# ProPrj_AD__2025-10-15.net
KiCad netlist of a schematic drawn in EasyEDA Pro
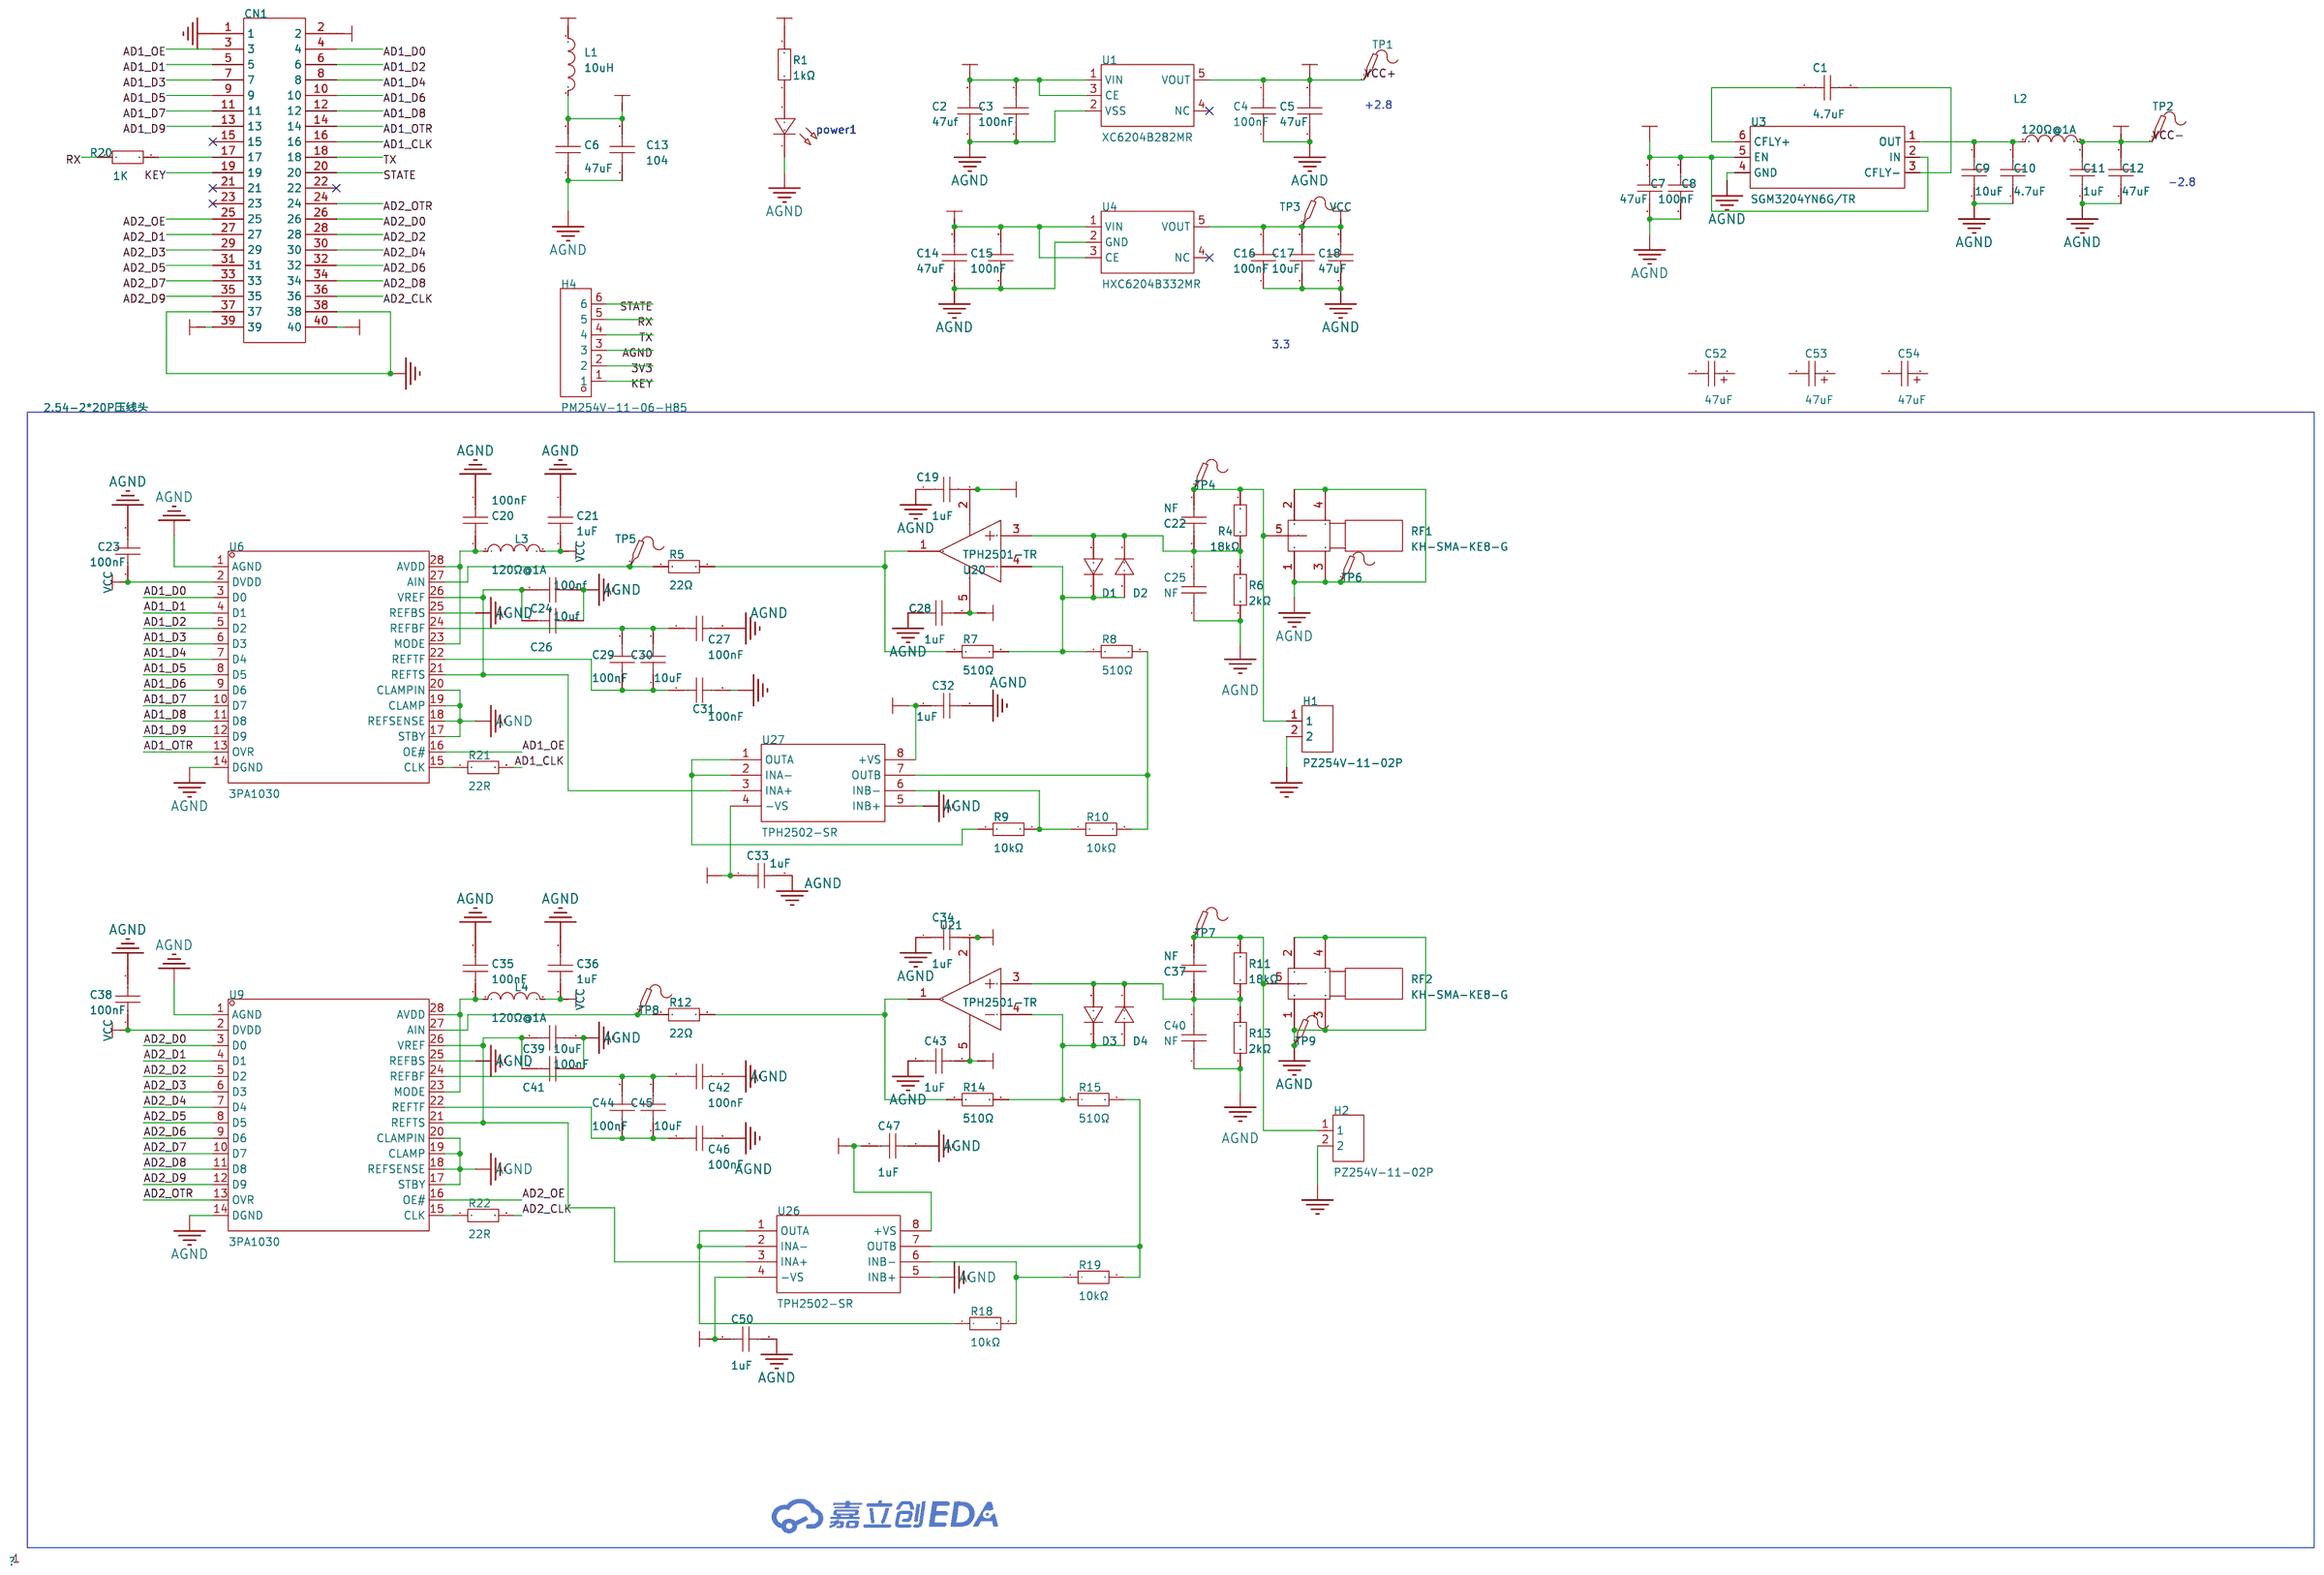
[diagram p0: schematic sheet]

(export (version "E")
  (design (tool "Eeschema 10.0.6"))
  (components
    (comp (ref "C1")
      (value "4.7uF")
      (footprint "easyedapro:C0603")
      (libsource (lib "easyedapro") (part "Capacitance"))
    )
    (comp (ref "C2")
      (value "47uf")
      (footprint "easyedapro:C0603")
      (libsource (lib "easyedapro") (part "Capacitance"))
    )
    (comp (ref "C3")
      (value "100nF")
      (footprint "easyedapro:C0603")
      (libsource (lib "easyedapro") (part "Capacitance"))
    )
    (comp (ref "C4")
      (value "100nF")
      (footprint "easyedapro:C0603")
      (libsource (lib "easyedapro") (part "Capacitance"))
    )
    (comp (ref "C5")
      (value "47uF")
      (footprint "easyedapro:C0603")
      (libsource (lib "easyedapro") (part "Capacitance"))
    )
    (comp (ref "C6")
      (value "47uF")
      (footprint "easyedapro:C0603")
      (libsource (lib "easyedapro") (part "Capacitance"))
    )
    (comp (ref "C7")
      (value "47uF")
      (footprint "easyedapro:C0603")
      (libsource (lib "easyedapro") (part "Capacitance"))
    )
    (comp (ref "C8")
      (value "100nF")
      (footprint "easyedapro:C0603")
      (libsource (lib "easyedapro") (part "Capacitance"))
    )
    (comp (ref "C9")
      (value "10uF")
      (footprint "easyedapro:C0603")
      (libsource (lib "easyedapro") (part "Capacitance"))
    )
    (comp (ref "C10")
      (value "4.7uF")
      (footprint "easyedapro:C0603")
      (libsource (lib "easyedapro") (part "Capacitance"))
    )
    (comp (ref "C11")
      (value "1uF")
      (footprint "easyedapro:C0603")
      (libsource (lib "easyedapro") (part "Capacitance"))
    )
    (comp (ref "C12")
      (value "47uF")
      (footprint "easyedapro:C0603")
      (libsource (lib "easyedapro") (part "Capacitance"))
    )
    (comp (ref "C13")
      (value "100nF")
      (footprint "easyedapro:C0603")
      (libsource (lib "easyedapro") (part "Capacitance"))
    )
    (comp (ref "C14")
      (value "47uF")
      (footprint "easyedapro:C0603")
      (libsource (lib "easyedapro") (part "Capacitance"))
    )
    (comp (ref "C15")
      (value "100nF")
      (footprint "easyedapro:C0603")
      (libsource (lib "easyedapro") (part "Capacitance"))
    )
    (comp (ref "C16")
      (value "100nF")
      (footprint "easyedapro:C0603")
      (libsource (lib "easyedapro") (part "Capacitance"))
    )
    (comp (ref "C17")
      (value "10uF")
      (footprint "easyedapro:C0603")
      (libsource (lib "easyedapro") (part "Capacitance"))
    )
    (comp (ref "C18")
      (value "47uF")
      (footprint "easyedapro:C0603")
      (libsource (lib "easyedapro") (part "Capacitance"))
    )
    (comp (ref "C19")
      (value "1uF")
      (footprint "easyedapro:C0603")
      (libsource (lib "easyedapro") (part "Capacitance"))
    )
    (comp (ref "C20")
      (value "100nF")
      (footprint "easyedapro:C0603")
      (libsource (lib "easyedapro") (part "Capacitance"))
    )
    (comp (ref "C21")
      (value "1uF")
      (footprint "easyedapro:C0603")
      (libsource (lib "easyedapro") (part "Capacitance"))
    )
    (comp (ref "C22")
      (value "NF")
      (footprint "easyedapro:C0603")
      (libsource (lib "easyedapro") (part "Capacitance"))
    )
    (comp (ref "C23")
      (value "100nF")
      (footprint "easyedapro:C0603")
      (libsource (lib "easyedapro") (part "Capacitance"))
    )
    (comp (ref "C24")
      (value "100nf")
      (footprint "easyedapro:C0603")
      (libsource (lib "easyedapro") (part "Capacitance"))
    )
    (comp (ref "C25")
      (value "NF")
      (footprint "easyedapro:C0603")
      (libsource (lib "easyedapro") (part "Capacitance"))
    )
    (comp (ref "C26")
      (value "10uf")
      (footprint "easyedapro:C0603")
      (libsource (lib "easyedapro") (part "Capacitance"))
    )
    (comp (ref "C27")
      (value "100nF")
      (footprint "easyedapro:C0603")
      (libsource (lib "easyedapro") (part "Capacitance"))
    )
    (comp (ref "C28")
      (value "1uF")
      (footprint "easyedapro:C0603")
      (libsource (lib "easyedapro") (part "Capacitance"))
    )
    (comp (ref "C29")
      (value "100nF")
      (footprint "easyedapro:C0603")
      (libsource (lib "easyedapro") (part "Capacitance"))
    )
    (comp (ref "C30")
      (value "10uF")
      (footprint "easyedapro:C0603")
      (libsource (lib "easyedapro") (part "Capacitance"))
    )
    (comp (ref "C31")
      (value "100nF")
      (footprint "easyedapro:C0603")
      (libsource (lib "easyedapro") (part "Capacitance"))
    )
    (comp (ref "C32")
      (value "1uF")
      (footprint "easyedapro:C0603")
      (libsource (lib "easyedapro") (part "Capacitance"))
    )
    (comp (ref "C33")
      (value "1uF")
      (footprint "easyedapro:C0603")
      (libsource (lib "easyedapro") (part "Capacitance"))
    )
    (comp (ref "C34")
      (value "1uF")
      (footprint "easyedapro:C0603")
      (libsource (lib "easyedapro") (part "Capacitance"))
    )
    (comp (ref "C35")
      (value "100nF")
      (footprint "easyedapro:C0603")
      (libsource (lib "easyedapro") (part "Capacitance"))
    )
    (comp (ref "C36")
      (value "1uF")
      (footprint "easyedapro:C0603")
      (libsource (lib "easyedapro") (part "Capacitance"))
    )
    (comp (ref "C37")
      (value "NF")
      (footprint "easyedapro:C0603")
      (libsource (lib "easyedapro") (part "Capacitance"))
    )
    (comp (ref "C38")
      (value "100nF")
      (footprint "easyedapro:C0603")
      (libsource (lib "easyedapro") (part "Capacitance"))
    )
    (comp (ref "C39")
      (value "10uF")
      (footprint "easyedapro:C0603")
      (libsource (lib "easyedapro") (part "Capacitance"))
    )
    (comp (ref "C40")
      (value "NF")
      (footprint "easyedapro:C0603")
      (libsource (lib "easyedapro") (part "Capacitance"))
    )
    (comp (ref "C41")
      (value "100nF")
      (footprint "easyedapro:C0603")
      (libsource (lib "easyedapro") (part "Capacitance"))
    )
    (comp (ref "C42")
      (value "100nF")
      (footprint "easyedapro:C0603")
      (libsource (lib "easyedapro") (part "Capacitance"))
    )
    (comp (ref "C43")
      (value "1uF")
      (footprint "easyedapro:C0603")
      (libsource (lib "easyedapro") (part "Capacitance"))
    )
    (comp (ref "C44")
      (value "100nF")
      (footprint "easyedapro:C0603")
      (libsource (lib "easyedapro") (part "Capacitance"))
    )
    (comp (ref "C45")
      (value "10uF")
      (footprint "easyedapro:C0603")
      (libsource (lib "easyedapro") (part "Capacitance"))
    )
    (comp (ref "C46")
      (value "100nF")
      (footprint "easyedapro:C0603")
      (libsource (lib "easyedapro") (part "Capacitance"))
    )
    (comp (ref "C47")
      (value "1uF")
      (footprint "easyedapro:C0603")
      (libsource (lib "easyedapro") (part "Capacitance"))
    )
    (comp (ref "C50")
      (value "1uF")
      (footprint "easyedapro:C0603")
      (libsource (lib "easyedapro") (part "Capacitance"))
    )
    (comp (ref "C52")
      (value "47uF")
      (footprint "easyedapro:CASE-D_7343")
      (description "容值:47uF;精度:±10%;额定电压:16V;等效串联电阻:900mΩ@100kHz;")
      (fields (field (name "Manufacturer Part") "TAJD476K016RNJ") (field (name "Manufacturer") "Kyocera AVX"))
      (libsource (lib "easyedapro") (part "TAJD476K016RNJ"))
    )
    (comp (ref "C53")
      (value "47uF")
      (footprint "easyedapro:CASE-D_7343")
      (description "容值:47uF;精度:±10%;额定电压:16V;等效串联电阻:900mΩ@100kHz;")
      (fields (field (name "Manufacturer Part") "TAJD476K016RNJ") (field (name "Manufacturer") "Kyocera AVX"))
      (libsource (lib "easyedapro") (part "TAJD476K016RNJ"))
    )
    (comp (ref "C54")
      (value "47uF")
      (footprint "easyedapro:CASE-D_7343")
      (description "容值:47uF;精度:±10%;额定电压:16V;等效串联电阻:900mΩ@100kHz;")
      (fields (field (name "Manufacturer Part") "TAJD476K016RNJ") (field (name "Manufacturer") "Kyocera AVX"))
      (libsource (lib "easyedapro") (part "TAJD476K016RNJ"))
    )
    (comp (ref "CN1")
      (value "2.54-2*20P压线头")
      (footprint "easyedapro:HDR-TH_40P-V-H-R2-P2.54")
      (description "连接器类型:IDC连接器;间距:2.54mm;安装方式:三件式(连接器+压排+反折盖);行距:2.54mm;排数:2;触头材质:黄铜;触头镀层:金;")
      (fields (field (name "Manufacturer") "BOOMELE(博穆精密)"))
      (libsource (lib "easyedapro") (part "Crimping terminals2*20"))
    )
    (comp (ref "D1")
      (value "1N4148W")
      (footprint "easyedapro:SOD-123F_L2.7-W1.6-LS3.8-RD")
      (description "二极管配置:独立式;正向压降(Vf):1V@50mA;直流反向耐压(Vr):75V;整流电流:150mA;反向恢复时间(Trr):4ns;")
      (fields (field (name "Manufacturer") "ST(先科)"))
      (libsource (lib "easyedapro") (part "1N4148W_C81598"))
    )
    (comp (ref "D2")
      (value "1N4148W")
      (footprint "easyedapro:SOD-123F_L2.7-W1.6-LS3.8-RD")
      (description "二极管配置:独立式;正向压降(Vf):1V@50mA;直流反向耐压(Vr):75V;整流电流:150mA;反向恢复时间(Trr):4ns;")
      (fields (field (name "Manufacturer") "ST(先科)"))
      (libsource (lib "easyedapro") (part "1N4148W_C81598"))
    )
    (comp (ref "D3")
      (value "1N4148W")
      (footprint "easyedapro:SOD-123F_L2.7-W1.6-LS3.8-RD")
      (description "二极管配置:独立式;正向压降(Vf):1V@50mA;直流反向耐压(Vr):75V;整流电流:150mA;反向恢复时间(Trr):4ns;")
      (fields (field (name "Manufacturer") "ST(先科)"))
      (libsource (lib "easyedapro") (part "1N4148W_C81598"))
    )
    (comp (ref "D4")
      (value "1N4148W")
      (footprint "easyedapro:SOD-123F_L2.7-W1.6-LS3.8-RD")
      (description "二极管配置:独立式;正向压降(Vf):1V@50mA;直流反向耐压(Vr):75V;整流电流:150mA;反向恢复时间(Trr):4ns;")
      (fields (field (name "Manufacturer") "ST(先科)"))
      (libsource (lib "easyedapro") (part "1N4148W_C81598"))
    )
    (comp (ref "H1")
      (value "PZ254V-11-02P")
      (footprint "easyedapro:HDR-TH_2P-P2.54-V-M")
      (fields (field (name "Manufacturer") "XFCN(兴飞)"))
      (libsource (lib "easyedapro") (part "PZ254V-11-02P"))
    )
    (comp (ref "H2")
      (value "PZ254V-11-02P")
      (footprint "easyedapro:HDR-TH_2P-P2.54-V-M")
      (fields (field (name "Manufacturer") "XFCN(兴飞)"))
      (libsource (lib "easyedapro") (part "PZ254V-11-02P"))
    )
    (comp (ref "H4")
      (value "PM254V-11-06-H85")
      (footprint "easyedapro:HDR-TH_6P-P2.54-V-F")
      (fields (field (name "Manufacturer") "XFCN(兴飞)"))
      (libsource (lib "easyedapro") (part "PM254V-11-06-H85"))
    )
    (comp (ref "L1")
      (value "10uH")
      (footprint "easyedapro:L0603")
      (description "电感值:10uH;精度:±10%;额定电流:3mA;饱和电流(Isat):-;直流电阻(DCR):1.85Ω;")
      (fields
        (field (name "Manufacturer Part") "SDFL1608S100KTF")
        (field (name "Manufacturer") "Sunlord(顺络)")
      )
      (libsource (lib "easyedapro") (part "SDFL1608S100KTF"))
    )
    (comp (ref "L2")
      (value "120Ω@1A")
      (footprint "easyedapro:L0603")
      (description "电感值:10uH;精度:±10%;额定电流:3mA;饱和电流(Isat):-;直流电阻(DCR):1.85Ω;")
      (fields
        (field (name "Manufacturer Part") "SDFL1608S100KTF")
        (field (name "Manufacturer") "Sunlord(顺络)")
      )
      (libsource (lib "easyedapro") (part "SDFL1608S100KTF"))
    )
    (comp (ref "L3")
      (value "120Ω@1A")
      (footprint "easyedapro:L0603")
      (description "电感值:10uH;精度:±10%;额定电流:3mA;饱和电流(Isat):-;直流电阻(DCR):1.85Ω;")
      (fields
        (field (name "Manufacturer Part") "SDFL1608S100KTF")
        (field (name "Manufacturer") "Sunlord(顺络)")
      )
      (libsource (lib "easyedapro") (part "SDFL1608S100KTF"))
    )
    (comp (ref "L4")
      (value "120Ω@1A")
      (footprint "easyedapro:L0603")
      (description "电感值:10uH;精度:±10%;额定电流:3mA;饱和电流(Isat):-;直流电阻(DCR):1.85Ω;")
      (fields
        (field (name "Manufacturer Part") "SDFL1608S100KTF")
        (field (name "Manufacturer") "Sunlord(顺络)")
      )
      (libsource (lib "easyedapro") (part "SDFL1608S100KTF"))
    )
    (comp (ref "power1")
      (value "LTST-C193TBKT-5A")
      (footprint "easyedapro:LED_0603")
      (libsource (lib "easyedapro") (part "LED_B"))
    )
    (comp (ref "R1") (value "1kΩ") (footprint "easyedapro:R0603") (libsource (lib "easyedapro") (part "电阻")))
    (comp (ref "R4") (value "18kΩ") (footprint "easyedapro:R0603") (libsource (lib "easyedapro") (part "电阻")))
    (comp (ref "R5") (value "22Ω") (footprint "easyedapro:R0603") (libsource (lib "easyedapro") (part "电阻")))
    (comp (ref "R6") (value "2kΩ") (footprint "easyedapro:R0603") (libsource (lib "easyedapro") (part "电阻")))
    (comp (ref "R7") (value "510Ω") (footprint "easyedapro:R0603") (libsource (lib "easyedapro") (part "电阻")))
    (comp (ref "R8") (value "510Ω") (footprint "easyedapro:R0603") (libsource (lib "easyedapro") (part "电阻")))
    (comp (ref "R9") (value "10kΩ") (footprint "easyedapro:R0603") (libsource (lib "easyedapro") (part "电阻")))
    (comp (ref "R10")
      (value "10kΩ")
      (footprint "easyedapro:R0603")
      (libsource (lib "easyedapro") (part "电阻"))
    )
    (comp (ref "R11")
      (value "18kΩ")
      (footprint "easyedapro:R0603")
      (libsource (lib "easyedapro") (part "电阻"))
    )
    (comp (ref "R12") (value "22Ω") (footprint "easyedapro:R0603") (libsource (lib "easyedapro") (part "电阻")))
    (comp (ref "R13") (value "2kΩ") (footprint "easyedapro:R0603") (libsource (lib "easyedapro") (part "电阻")))
    (comp (ref "R14")
      (value "510Ω")
      (footprint "easyedapro:R0603")
      (libsource (lib "easyedapro") (part "电阻"))
    )
    (comp (ref "R15")
      (value "510Ω")
      (footprint "easyedapro:R0603")
      (libsource (lib "easyedapro") (part "电阻"))
    )
    (comp (ref "R18")
      (value "10kΩ")
      (footprint "easyedapro:R0603")
      (libsource (lib "easyedapro") (part "电阻"))
    )
    (comp (ref "R19")
      (value "10kΩ")
      (footprint "easyedapro:R0603")
      (libsource (lib "easyedapro") (part "电阻"))
    )
    (comp (ref "R20") (value "1K") (footprint "easyedapro:R0603") (libsource (lib "easyedapro") (part "电阻")))
    (comp (ref "R21") (value "22R") (footprint "easyedapro:R0603") (libsource (lib "easyedapro") (part "电阻")))
    (comp (ref "R22") (value "22R") (footprint "easyedapro:R0603") (libsource (lib "easyedapro") (part "电阻")))
    (comp (ref "RF1")
      (value "KH-SMA-KE8-G")
      (footprint "easyedapro:CONN-SMD_KH-SMA-KE8-G")
      (description "连接器类型:板端;接口类型:内孔;端口数量:1;接口直径:-;接口长度/高度:8mm;频率-最大值:-;射频系列:SMA;阻抗:-;样式:偏脚;工作温度范围:-;")
      (fields (field (name "Manufacturer") "kinghelm(金航标)"))
      (libsource (lib "easyedapro") (part "KH-SMA-KE8-G"))
    )
    (comp (ref "RF2")
      (value "KH-SMA-KE8-G")
      (footprint "easyedapro:CONN-SMD_KH-SMA-KE8-G")
      (description "连接器类型:板端;接口类型:内孔;端口数量:1;接口直径:-;接口长度/高度:8mm;频率-最大值:-;射频系列:SMA;阻抗:-;样式:偏脚;工作温度范围:-;")
      (fields (field (name "Manufacturer") "kinghelm(金航标)"))
      (libsource (lib "easyedapro") (part "KH-SMA-KE8-G"))
    )
    (comp (ref "TP1")
      (value "~")
      (footprint "easyedapro:Test-Point-0.5mm")
      (description "Test Point 测试点")
      (libsource (lib "easyedapro") (part "Test-Point"))
    )
    (comp (ref "TP2")
      (value "~")
      (footprint "easyedapro:Test-Point-0.5mm")
      (description "Test Point 测试点")
      (libsource (lib "easyedapro") (part "Test-Point"))
    )
    (comp (ref "TP3")
      (value "~")
      (footprint "easyedapro:Test-Point-0.5mm")
      (description "Test Point 测试点")
      (libsource (lib "easyedapro") (part "Test-Point"))
    )
    (comp (ref "TP4")
      (value "~")
      (footprint "easyedapro:Test-Point-0.5mm")
      (description "Test Point 测试点")
      (libsource (lib "easyedapro") (part "Test-Point"))
    )
    (comp (ref "TP5")
      (value "~")
      (footprint "easyedapro:Test-Point-0.5mm")
      (description "Test Point 测试点")
      (libsource (lib "easyedapro") (part "Test-Point"))
    )
    (comp (ref "TP6")
      (value "~")
      (footprint "easyedapro:Test-Point-0.5mm")
      (description "Test Point 测试点")
      (libsource (lib "easyedapro") (part "Test-Point"))
    )
    (comp (ref "TP7")
      (value "~")
      (footprint "easyedapro:Test-Point-0.5mm")
      (description "Test Point 测试点")
      (libsource (lib "easyedapro") (part "Test-Point"))
    )
    (comp (ref "TP8")
      (value "~")
      (footprint "easyedapro:Test-Point-0.5mm")
      (description "Test Point 测试点")
      (libsource (lib "easyedapro") (part "Test-Point"))
    )
    (comp (ref "TP9")
      (value "~")
      (footprint "easyedapro:Test-Point-0.5mm")
      (description "Test Point 测试点")
      (libsource (lib "easyedapro") (part "Test-Point"))
    )
    (comp (ref "U1")
      (value "XC6204B282MR")
      (footprint "easyedapro:SOT-23-5_L2.9-W1.6-P0.95-LS2.8-BR")
      (description "输出类型:固定;工作电压:24V;输出电压:2.8V;输出电流:300mA;电源纹波抑制比(PSRR):-;输出极性:正极;")
      (fields (field (name "Manufacturer") "TECH PUBLIC(台舟)"))
      (libsource (lib "easyedapro") (part "XC6204B282MR_C18212677"))
    )
    (comp (ref "U3")
      (value "SGM3204YN6G/TR")
      (footprint "easyedapro:SOT-23-6_L2.9-W1.6-P0.95-LS2.8-BR")
      (description "电荷泵芯片，开关电容式电压变换器，最大输出200mA,可用于运放放大、滤波等电路")
      (fields (field (name "Manufacturer") "SGMICRO(圣邦微)"))
      (libsource (lib "easyedapro") (part "SGM3204YN6G/TR"))
    )
    (comp (ref "U4")
      (value "HXC6204B332MR")
      (footprint "easyedapro:SOT-23-5_L3.0-W1.7-P0.95-LS2.8-BR")
      (description "输出类型:固定;工作电压:6V;输出电压:3.3V;输出电流:300mA;电源纹波抑制比(PSRR):75dB@(1kHz);输出极性:正极;")
      (fields (field (name "Manufacturer") "HXY MOSFET(华轩阳电子)"))
      (libsource (lib "easyedapro") (part "HXC6204B332MR"))
    )
    (comp (ref "U6")
      (value "3PA1030")
      (footprint "easyedapro:TSSOP-28_L9.7-W4.4-P0.65-LS6.4-BL")
      (description "分辨率:10位;采样率:50MHz;工作电压:2.7V~5.5V;接口类型:-;")
      (fields (field (name "Manufacturer") "3PEAK(思瑞浦)"))
      (libsource (lib "easyedapro") (part "3PA1030"))
    )
    (comp (ref "U9")
      (value "3PA1030")
      (footprint "easyedapro:TSSOP-28_L9.7-W4.4-P0.65-LS6.4-BL")
      (description "分辨率:10位;采样率:50MHz;工作电压:2.7V~5.5V;接口类型:-;")
      (fields (field (name "Manufacturer") "3PEAK(思瑞浦)"))
      (libsource (lib "easyedapro") (part "3PA1030"))
    )
    (comp (ref "U20")
      (value "TPH2501-TR")
      (footprint "easyedapro:SOT-23-5_L3.0-W1.7-P0.95-LS2.8-BR")
      (description "放大器数:单路;轨到轨:-;增益带宽积(GBP):50MHz;压摆率(SR):25V/us;输入偏置电流(Ib):0.2pA;")
      (fields (field (name "Manufacturer") "TI(德州仪器)"))
      (libsource (lib "easyedapro") (part "OPA365AIDBVR"))
    )
    (comp (ref "U21")
      (value "TPH2501-TR")
      (footprint "easyedapro:SOT-23-5_L3.0-W1.7-P0.95-LS2.8-BR")
      (description "放大器数:单路;轨到轨:-;增益带宽积(GBP):50MHz;压摆率(SR):25V/us;输入偏置电流(Ib):0.2pA;")
      (fields (field (name "Manufacturer") "TI(德州仪器)"))
      (libsource (lib "easyedapro") (part "OPA365AIDBVR"))
    )
    (comp (ref "U26")
      (value "TPH2502-SR")
      (footprint "easyedapro:SOP-8_L4.9-W3.9-P1.27-LS6.0-BL")
      (description "放大器数:双路;轨到轨:轨到轨输入,轨到轨输出;增益带宽积(GBP):120MHz;输入失调电压(Vos):50uV;压摆率(SR):180V/us;输入偏置电流(Ib):0.3pA;")
      (fields (field (name "Manufacturer") "3PEAK(思瑞浦)"))
      (libsource (lib "easyedapro") (part "TPH2502-SR"))
    )
    (comp (ref "U27")
      (value "TPH2502-SR")
      (footprint "easyedapro:SOP-8_L4.9-W3.9-P1.27-LS6.0-BL")
      (description "放大器数:双路;轨到轨:轨到轨输入,轨到轨输出;增益带宽积(GBP):120MHz;输入失调电压(Vos):50uV;压摆率(SR):180V/us;输入偏置电流(Ib):0.3pA;")
      (fields (field (name "Manufacturer") "3PEAK(思瑞浦)"))
      (libsource (lib "easyedapro") (part "TPH2502-SR"))
    )
  )
  (nets
    (net (code "1") (name "/AD1_CLK") (class "Default")
      (node (ref "CN1") (pin "16") (pinfunction "16_16") (pintype "unspecified"))
      (node (ref "R21") (pin "2") (pinfunction "2_2") (pintype "input"))
    )
    (net (code "2") (name "/AD1_D0") (class "Default")
      (node (ref "CN1") (pin "4") (pinfunction "4_4") (pintype "unspecified"))
      (node (ref "U6") (pin "3") (pinfunction "D0_3") (pintype "unspecified"))
    )
    (net (code "3") (name "/AD1_D1") (class "Default")
      (node (ref "CN1") (pin "5") (pinfunction "5_5") (pintype "unspecified"))
      (node (ref "U6") (pin "4") (pinfunction "D1_4") (pintype "unspecified"))
    )
    (net (code "4") (name "/AD1_D2") (class "Default")
      (node (ref "CN1") (pin "6") (pinfunction "6_6") (pintype "unspecified"))
      (node (ref "U6") (pin "5") (pinfunction "D2_5") (pintype "unspecified"))
    )
    (net (code "5") (name "/AD1_D3") (class "Default")
      (node (ref "CN1") (pin "7") (pinfunction "7_7") (pintype "unspecified"))
      (node (ref "U6") (pin "6") (pinfunction "D3_6") (pintype "unspecified"))
    )
    (net (code "6") (name "/AD1_D4") (class "Default")
      (node (ref "CN1") (pin "8") (pinfunction "8_8") (pintype "unspecified"))
      (node (ref "U6") (pin "7") (pinfunction "D4_7") (pintype "unspecified"))
    )
    (net (code "7") (name "/AD1_D5") (class "Default")
      (node (ref "CN1") (pin "9") (pinfunction "9_9") (pintype "unspecified"))
      (node (ref "U6") (pin "8") (pinfunction "D5_8") (pintype "unspecified"))
    )
    (net (code "8") (name "/AD1_D6") (class "Default")
      (node (ref "CN1") (pin "10") (pinfunction "10_10") (pintype "unspecified"))
      (node (ref "U6") (pin "9") (pinfunction "D6_9") (pintype "unspecified"))
    )
    (net (code "9") (name "/AD1_D7") (class "Default")
      (node (ref "CN1") (pin "11") (pinfunction "11_11") (pintype "unspecified"))
      (node (ref "U6") (pin "10") (pinfunction "D7_10") (pintype "unspecified"))
    )
    (net (code "10") (name "/AD1_D8") (class "Default")
      (node (ref "CN1") (pin "12") (pinfunction "12_12") (pintype "unspecified"))
      (node (ref "U6") (pin "11") (pinfunction "D8_11") (pintype "unspecified"))
    )
    (net (code "11") (name "/AD1_D9") (class "Default")
      (node (ref "CN1") (pin "13") (pinfunction "13_13") (pintype "unspecified"))
      (node (ref "U6") (pin "12") (pinfunction "D9_12") (pintype "unspecified"))
    )
    (net (code "12") (name "/AD1_OE") (class "Default")
      (node (ref "CN1") (pin "3") (pinfunction "3_3") (pintype "unspecified"))
      (node (ref "U6") (pin "16") (pinfunction "OE#_16") (pintype "unspecified"))
    )
    (net (code "13") (name "/AD1_OTR") (class "Default")
      (node (ref "CN1") (pin "14") (pinfunction "14_14") (pintype "unspecified"))
      (node (ref "U6") (pin "13") (pinfunction "OVR_13") (pintype "unspecified"))
    )
    (net (code "14") (name "/AD2_CLK") (class "Default")
      (node (ref "CN1") (pin "36") (pinfunction "36_36") (pintype "unspecified"))
      (node (ref "R22") (pin "2") (pinfunction "2_2") (pintype "input"))
    )
    (net (code "15") (name "/AD2_D0") (class "Default")
      (node (ref "CN1") (pin "26") (pinfunction "26_26") (pintype "unspecified"))
      (node (ref "U9") (pin "3") (pinfunction "D0_3") (pintype "unspecified"))
    )
    (net (code "16") (name "/AD2_D1") (class "Default")
      (node (ref "CN1") (pin "27") (pinfunction "27_27") (pintype "unspecified"))
      (node (ref "U9") (pin "4") (pinfunction "D1_4") (pintype "unspecified"))
    )
    (net (code "17") (name "/AD2_D2") (class "Default")
      (node (ref "CN1") (pin "28") (pinfunction "28_28") (pintype "unspecified"))
      (node (ref "U9") (pin "5") (pinfunction "D2_5") (pintype "unspecified"))
    )
    (net (code "18") (name "/AD2_D3") (class "Default")
      (node (ref "CN1") (pin "29") (pinfunction "29_29") (pintype "unspecified"))
      (node (ref "U9") (pin "6") (pinfunction "D3_6") (pintype "unspecified"))
    )
    (net (code "19") (name "/AD2_D4") (class "Default")
      (node (ref "CN1") (pin "30") (pinfunction "30_30") (pintype "unspecified"))
      (node (ref "U9") (pin "7") (pinfunction "D4_7") (pintype "unspecified"))
    )
    (net (code "20") (name "/AD2_D5") (class "Default")
      (node (ref "CN1") (pin "31") (pinfunction "31_31") (pintype "unspecified"))
      (node (ref "U9") (pin "8") (pinfunction "D5_8") (pintype "unspecified"))
    )
    (net (code "21") (name "/AD2_D6") (class "Default")
      (node (ref "CN1") (pin "32") (pinfunction "32_32") (pintype "unspecified"))
      (node (ref "U9") (pin "9") (pinfunction "D6_9") (pintype "unspecified"))
    )
    (net (code "22") (name "/AD2_D7") (class "Default")
      (node (ref "CN1") (pin "33") (pinfunction "33_33") (pintype "unspecified"))
      (node (ref "U9") (pin "10") (pinfunction "D7_10") (pintype "unspecified"))
    )
    (net (code "23") (name "/AD2_D8") (class "Default")
      (node (ref "CN1") (pin "34") (pinfunction "34_34") (pintype "unspecified"))
      (node (ref "U9") (pin "11") (pinfunction "D8_11") (pintype "unspecified"))
    )
    (net (code "24") (name "/AD2_D9") (class "Default")
      (node (ref "CN1") (pin "35") (pinfunction "35_35") (pintype "unspecified"))
      (node (ref "U9") (pin "12") (pinfunction "D9_12") (pintype "unspecified"))
    )
    (net (code "25") (name "/AD2_OE") (class "Default")
      (node (ref "CN1") (pin "25") (pinfunction "25_25") (pintype "unspecified"))
      (node (ref "U9") (pin "16") (pinfunction "OE#_16") (pintype "unspecified"))
    )
    (net (code "26") (name "/AD2_OTR") (class "Default")
      (node (ref "CN1") (pin "24") (pinfunction "24_24") (pintype "unspecified"))
      (node (ref "U9") (pin "13") (pinfunction "OVR_13") (pintype "unspecified"))
    )
    (net (code "27") (name "/KEY") (class "Default")
      (node (ref "CN1") (pin "19") (pinfunction "19_19") (pintype "unspecified"))
      (node (ref "H4") (pin "1") (pinfunction "1_1") (pintype "unspecified"))
    )
    (net (code "28") (name "/RX") (class "Default")
      (node (ref "H4") (pin "5") (pinfunction "5_5") (pintype "unspecified"))
      (node (ref "R20") (pin "1") (pinfunction "1_1") (pintype "input"))
    )
    (net (code "29") (name "/STATE") (class "Default")
      (node (ref "CN1") (pin "20") (pinfunction "20_20") (pintype "unspecified"))
      (node (ref "H4") (pin "6") (pinfunction "6_6") (pintype "unspecified"))
    )
    (net (code "30") (name "/TX") (class "Default")
      (node (ref "CN1") (pin "18") (pinfunction "18_18") (pintype "unspecified"))
      (node (ref "H4") (pin "4") (pinfunction "4_4") (pintype "unspecified"))
    )
    (net (code "31") (name "3V3") (class "Default")
      (node (ref "CN1") (pin "39") (pinfunction "39_39") (pintype "unspecified"))
      (node (ref "CN1") (pin "40") (pinfunction "40_40") (pintype "unspecified"))
      (node (ref "H4") (pin "2") (pinfunction "2_2") (pintype "unspecified"))
    )
    (net (code "32") (name "AGND") (class "Default")
      (node (ref "C10") (pin "1") (pinfunction "1_1") (pintype "input"))
      (node (ref "C11") (pin "1") (pinfunction "1_1") (pintype "input"))
      (node (ref "C12") (pin "1") (pinfunction "1_1") (pintype "input"))
      (node (ref "C13") (pin "1") (pinfunction "1_1") (pintype "input"))
      (node (ref "C14") (pin "1") (pinfunction "1_1") (pintype "input"))
      (node (ref "C15") (pin "1") (pinfunction "1_1") (pintype "input"))
      (node (ref "C16") (pin "1") (pinfunction "1_1") (pintype "input"))
      (node (ref "C17") (pin "1") (pinfunction "1_1") (pintype "input"))
      (node (ref "C18") (pin "1") (pinfunction "1_1") (pintype "input"))
      (node (ref "C19") (pin "1") (pinfunction "1_1") (pintype "input"))
      (node (ref "C2") (pin "1") (pinfunction "1_1") (pintype "input"))
      (node (ref "C20") (pin "2") (pinfunction "2_2") (pintype "input"))
      (node (ref "C21") (pin "2") (pinfunction "2_2") (pintype "input"))
      (node (ref "C23") (pin "2") (pinfunction "2_2") (pintype "input"))
      (node (ref "C24") (pin "2") (pinfunction "2_2") (pintype "input"))
      (node (ref "C25") (pin "1") (pinfunction "1_1") (pintype "input"))
      (node (ref "C26") (pin "2") (pinfunction "2_2") (pintype "input"))
      (node (ref "C27") (pin "2") (pinfunction "2_2") (pintype "input"))
      (node (ref "C28") (pin "1") (pinfunction "1_1") (pintype "input"))
      (node (ref "C3") (pin "1") (pinfunction "1_1") (pintype "input"))
      (node (ref "C31") (pin "2") (pinfunction "2_2") (pintype "input"))
      (node (ref "C32") (pin "2") (pinfunction "2_2") (pintype "input"))
      (node (ref "C33") (pin "2") (pinfunction "2_2") (pintype "input"))
      (node (ref "C34") (pin "1") (pinfunction "1_1") (pintype "input"))
      (node (ref "C35") (pin "2") (pinfunction "2_2") (pintype "input"))
      (node (ref "C36") (pin "2") (pinfunction "2_2") (pintype "input"))
      (node (ref "C38") (pin "2") (pinfunction "2_2") (pintype "input"))
      (node (ref "C39") (pin "2") (pinfunction "2_2") (pintype "input"))
      (node (ref "C4") (pin "1") (pinfunction "1_1") (pintype "input"))
      (node (ref "C40") (pin "1") (pinfunction "1_1") (pintype "input"))
      (node (ref "C41") (pin "2") (pinfunction "2_2") (pintype "input"))
      (node (ref "C42") (pin "2") (pinfunction "2_2") (pintype "input"))
      (node (ref "C43") (pin "1") (pinfunction "1_1") (pintype "input"))
      (node (ref "C46") (pin "2") (pinfunction "2_2") (pintype "input"))
      (node (ref "C47") (pin "2") (pinfunction "2_2") (pintype "input"))
      (node (ref "C5") (pin "1") (pinfunction "1_1") (pintype "input"))
      (node (ref "C50") (pin "2") (pinfunction "2_2") (pintype "input"))
      (node (ref "C6") (pin "1") (pinfunction "1_1") (pintype "input"))
      (node (ref "C7") (pin "1") (pinfunction "1_1") (pintype "input"))
      (node (ref "C8") (pin "1") (pinfunction "1_1") (pintype "input"))
      (node (ref "C9") (pin "1") (pinfunction "1_1") (pintype "input"))
      (node (ref "CN1") (pin "1") (pinfunction "1_1") (pintype "unspecified"))
      (node (ref "CN1") (pin "37") (pinfunction "37_37") (pintype "unspecified"))
      (node (ref "CN1") (pin "38") (pinfunction "38_38") (pintype "unspecified"))
      (node (ref "H1") (pin "2") (pinfunction "2_2") (pintype "unspecified"))
      (node (ref "H2") (pin "2") (pinfunction "2_2") (pintype "unspecified"))
      (node (ref "H4") (pin "3") (pinfunction "3_3") (pintype "unspecified"))
      (node (ref "R13") (pin "2") (pinfunction "2_2") (pintype "input"))
      (node (ref "R6") (pin "2") (pinfunction "2_2") (pintype "input"))
      (node (ref "RF1") (pin "1") (pinfunction "1_1") (pintype "unspecified"))
      (node (ref "RF1") (pin "2") (pinfunction "2_2") (pintype "unspecified"))
      (node (ref "RF1") (pin "3") (pinfunction "3_3") (pintype "unspecified"))
      (node (ref "RF1") (pin "4") (pinfunction "4_4") (pintype "unspecified"))
      (node (ref "RF2") (pin "1") (pinfunction "1_1") (pintype "unspecified"))
      (node (ref "RF2") (pin "2") (pinfunction "2_2") (pintype "unspecified"))
      (node (ref "RF2") (pin "3") (pinfunction "3_3") (pintype "unspecified"))
      (node (ref "RF2") (pin "4") (pinfunction "4_4") (pintype "unspecified"))
      (node (ref "TP6") (pin "1") (pinfunction "1_1") (pintype "input"))
      (node (ref "TP9") (pin "1") (pinfunction "1_1") (pintype "input"))
      (node (ref "U1") (pin "2") (pinfunction "VSS_2") (pintype "unspecified"))
      (node (ref "U26") (pin "5") (pinfunction "INB+_5") (pintype "unspecified"))
      (node (ref "U27") (pin "5") (pinfunction "INB+_5") (pintype "unspecified"))
      (node (ref "U3") (pin "4") (pinfunction "GND_4") (pintype "unspecified"))
      (node (ref "U4") (pin "2") (pinfunction "GND_2") (pintype "unspecified"))
      (node (ref "U6") (pin "1") (pinfunction "AGND_1") (pintype "unspecified"))
      (node (ref "U6") (pin "14") (pinfunction "DGND_14") (pintype "unspecified"))
      (node (ref "U6") (pin "17") (pinfunction "STBY_17") (pintype "unspecified"))
      (node (ref "U6") (pin "18") (pinfunction "REFSENSE_18") (pintype "unspecified"))
      (node (ref "U6") (pin "19") (pinfunction "CLAMP_19") (pintype "unspecified"))
      (node (ref "U6") (pin "20") (pinfunction "CLAMPIN_20") (pintype "unspecified"))
      (node (ref "U6") (pin "25") (pinfunction "REFBS_25") (pintype "unspecified"))
      (node (ref "U9") (pin "1") (pinfunction "AGND_1") (pintype "unspecified"))
      (node (ref "U9") (pin "14") (pinfunction "DGND_14") (pintype "unspecified"))
      (node (ref "U9") (pin "17") (pinfunction "STBY_17") (pintype "unspecified"))
      (node (ref "U9") (pin "18") (pinfunction "REFSENSE_18") (pintype "unspecified"))
      (node (ref "U9") (pin "19") (pinfunction "CLAMP_19") (pintype "unspecified"))
      (node (ref "U9") (pin "20") (pinfunction "CLAMPIN_20") (pintype "unspecified"))
      (node (ref "U9") (pin "25") (pinfunction "REFBS_25") (pintype "unspecified"))
      (node (ref "power1") (pin "1") (pinfunction "C_1") (pintype "input"))
    )
    (net (code "33") (name "Net-(C22-Pad2)") (class "Default")
      (node (ref "C22") (pin "2") (pinfunction "2_2") (pintype "input"))
      (node (ref "H1") (pin "1") (pinfunction "1_1") (pintype "unspecified"))
      (node (ref "R4") (pin "2") (pinfunction "2_2") (pintype "input"))
      (node (ref "RF1") (pin "5") (pinfunction "5_5") (pintype "unspecified"))
      (node (ref "TP4") (pin "1") (pinfunction "1_1") (pintype "input"))
    )
    (net (code "34") (name "Net-(C37-Pad2)") (class "Default")
      (node (ref "C37") (pin "2") (pinfunction "2_2") (pintype "input"))
      (node (ref "H2") (pin "1") (pinfunction "1_1") (pintype "unspecified"))
      (node (ref "R11") (pin "2") (pinfunction "2_2") (pintype "input"))
      (node (ref "RF2") (pin "5") (pinfunction "5_5") (pintype "unspecified"))
      (node (ref "TP7") (pin "1") (pinfunction "1_1") (pintype "input"))
    )
    (net (code "35") (name "Net-(CN1-Pad17)") (class "Default")
      (node (ref "CN1") (pin "17") (pinfunction "17_17") (pintype "unspecified"))
      (node (ref "R20") (pin "2") (pinfunction "2_2") (pintype "input"))
    )
    (net (code "36") (name "Net-(D1-A)") (class "Default")
      (node (ref "C22") (pin "1") (pinfunction "1_1") (pintype "input"))
      (node (ref "C25") (pin "2") (pinfunction "2_2") (pintype "input"))
      (node (ref "D1") (pin "2") (pinfunction "A_2") (pintype "unspecified"))
      (node (ref "D2") (pin "1") (pinfunction "K_1") (pintype "unspecified"))
      (node (ref "R4") (pin "1") (pinfunction "1_1") (pintype "input"))
      (node (ref "R6") (pin "1") (pinfunction "1_1") (pintype "input"))
      (node (ref "U20") (pin "3") (pinfunction "IN+_3") (pintype "unspecified"))
    )
    (net (code "37") (name "Net-(D1-K)") (class "Default")
      (node (ref "D1") (pin "1") (pinfunction "K_1") (pintype "unspecified"))
      (node (ref "D2") (pin "2") (pinfunction "A_2") (pintype "unspecified"))
      (node (ref "R7") (pin "2") (pinfunction "2_2") (pintype "input"))
      (node (ref "R8") (pin "1") (pinfunction "1_1") (pintype "input"))
      (node (ref "U20") (pin "4") (pinfunction "IN-_4") (pintype "unspecified"))
    )
    (net (code "38") (name "Net-(D3-A)") (class "Default")
      (node (ref "C37") (pin "1") (pinfunction "1_1") (pintype "input"))
      (node (ref "C40") (pin "2") (pinfunction "2_2") (pintype "input"))
      (node (ref "D3") (pin "2") (pinfunction "A_2") (pintype "unspecified"))
      (node (ref "D4") (pin "1") (pinfunction "K_1") (pintype "unspecified"))
      (node (ref "R11") (pin "1") (pinfunction "1_1") (pintype "input"))
      (node (ref "R13") (pin "1") (pinfunction "1_1") (pintype "input"))
      (node (ref "U21") (pin "3") (pinfunction "IN+_3") (pintype "unspecified"))
    )
    (net (code "39") (name "Net-(D3-K)") (class "Default")
      (node (ref "D3") (pin "1") (pinfunction "K_1") (pintype "unspecified"))
      (node (ref "D4") (pin "2") (pinfunction "A_2") (pintype "unspecified"))
      (node (ref "R14") (pin "2") (pinfunction "2_2") (pintype "input"))
      (node (ref "R15") (pin "1") (pinfunction "1_1") (pintype "input"))
      (node (ref "U21") (pin "4") (pinfunction "IN-_4") (pintype "unspecified"))
    )
    (net (code "40") (name "Net-(U3-CFLY+)") (class "Default")
      (node (ref "C1") (pin "1") (pinfunction "1_1") (pintype "input"))
      (node (ref "U3") (pin "6") (pinfunction "CFLY+_6") (pintype "unspecified"))
    )
    (net (code "41") (name "Net-(U3-CFLY-)") (class "Default")
      (node (ref "C1") (pin "2") (pinfunction "2_2") (pintype "input"))
      (node (ref "U3") (pin "3") (pinfunction "CFLY-_3") (pintype "unspecified"))
    )
    (net (code "42") (name "Net-(U3-OUT)") (class "Default")
      (node (ref "C10") (pin "2") (pinfunction "2_2") (pintype "input"))
      (node (ref "C9") (pin "2") (pinfunction "2_2") (pintype "input"))
      (node (ref "L2") (pin "1") (pinfunction "1_1") (pintype "unspecified"))
      (node (ref "U3") (pin "1") (pinfunction "OUT_1") (pintype "unspecified"))
    )
    (net (code "43") (name "Net-(U6-AIN)") (class "Default")
      (node (ref "R5") (pin "1") (pinfunction "1_1") (pintype "input"))
      (node (ref "TP5") (pin "1") (pinfunction "1_1") (pintype "input"))
      (node (ref "U6") (pin "27") (pinfunction "AIN_27") (pintype "unspecified"))
    )
    (net (code "44") (name "Net-(U6-AVDD)") (class "Default")
      (node (ref "C20") (pin "1") (pinfunction "1_1") (pintype "input"))
      (node (ref "L3") (pin "1") (pinfunction "1_1") (pintype "unspecified"))
      (node (ref "U6") (pin "23") (pinfunction "MODE_23") (pintype "unspecified"))
      (node (ref "U6") (pin "28") (pinfunction "AVDD_28") (pintype "unspecified"))
    )
    (net (code "45") (name "Net-(U6-CLK)") (class "Default")
      (node (ref "R21") (pin "1") (pinfunction "1_1") (pintype "input"))
      (node (ref "U6") (pin "15") (pinfunction "CLK_15") (pintype "unspecified"))
    )
    (net (code "46") (name "Net-(U6-REFBF)") (class "Default")
      (node (ref "C27") (pin "1") (pinfunction "1_1") (pintype "input"))
      (node (ref "C29") (pin "2") (pinfunction "2_2") (pintype "input"))
      (node (ref "C30") (pin "2") (pinfunction "2_2") (pintype "input"))
      (node (ref "U6") (pin "24") (pinfunction "REFBF_24") (pintype "unspecified"))
    )
    (net (code "47") (name "Net-(U6-REFTF)") (class "Default")
      (node (ref "C29") (pin "1") (pinfunction "1_1") (pintype "input"))
      (node (ref "C30") (pin "1") (pinfunction "1_1") (pintype "input"))
      (node (ref "C31") (pin "1") (pinfunction "1_1") (pintype "input"))
      (node (ref "U6") (pin "22") (pinfunction "REFTF_22") (pintype "unspecified"))
    )
    (net (code "48") (name "Net-(U9-AIN)") (class "Default")
      (node (ref "R12") (pin "1") (pinfunction "1_1") (pintype "input"))
      (node (ref "TP8") (pin "1") (pinfunction "1_1") (pintype "input"))
      (node (ref "U9") (pin "27") (pinfunction "AIN_27") (pintype "unspecified"))
    )
    (net (code "49") (name "Net-(U9-AVDD)") (class "Default")
      (node (ref "C35") (pin "1") (pinfunction "1_1") (pintype "input"))
      (node (ref "L4") (pin "1") (pinfunction "1_1") (pintype "unspecified"))
      (node (ref "U9") (pin "23") (pinfunction "MODE_23") (pintype "unspecified"))
      (node (ref "U9") (pin "28") (pinfunction "AVDD_28") (pintype "unspecified"))
    )
    (net (code "50") (name "Net-(U9-CLK)") (class "Default")
      (node (ref "R22") (pin "1") (pinfunction "1_1") (pintype "input"))
      (node (ref "U9") (pin "15") (pinfunction "CLK_15") (pintype "unspecified"))
    )
    (net (code "51") (name "Net-(U9-REFBF)") (class "Default")
      (node (ref "C42") (pin "1") (pinfunction "1_1") (pintype "input"))
      (node (ref "C44") (pin "2") (pinfunction "2_2") (pintype "input"))
      (node (ref "C45") (pin "2") (pinfunction "2_2") (pintype "input"))
      (node (ref "U9") (pin "24") (pinfunction "REFBF_24") (pintype "unspecified"))
    )
    (net (code "52") (name "Net-(U9-REFTF)") (class "Default")
      (node (ref "C44") (pin "1") (pinfunction "1_1") (pintype "input"))
      (node (ref "C45") (pin "1") (pinfunction "1_1") (pintype "input"))
      (node (ref "C46") (pin "1") (pinfunction "1_1") (pintype "input"))
      (node (ref "U9") (pin "22") (pinfunction "REFTF_22") (pintype "unspecified"))
    )
    (net (code "53") (name "Net-(U20-OUT)") (class "Default")
      (node (ref "R5") (pin "2") (pinfunction "2_2") (pintype "input"))
      (node (ref "R7") (pin "1") (pinfunction "1_1") (pintype "input"))
      (node (ref "U20") (pin "1") (pinfunction "OUT_1") (pintype "output"))
    )
    (net (code "54") (name "Net-(U21-OUT)") (class "Default")
      (node (ref "R12") (pin "2") (pinfunction "2_2") (pintype "input"))
      (node (ref "R14") (pin "1") (pinfunction "1_1") (pintype "input"))
      (node (ref "U21") (pin "1") (pinfunction "OUT_1") (pintype "output"))
    )
    (net (code "55") (name "Net-(U26-INA+)") (class "Default")
      (node (ref "C39") (pin "1") (pinfunction "1_1") (pintype "input"))
      (node (ref "C41") (pin "1") (pinfunction "1_1") (pintype "input"))
      (node (ref "U26") (pin "3") (pinfunction "INA+_3") (pintype "unspecified"))
      (node (ref "U9") (pin "21") (pinfunction "REFTS_21") (pintype "unspecified"))
      (node (ref "U9") (pin "26") (pinfunction "VREF_26") (pintype "unspecified"))
    )
    (net (code "56") (name "Net-(U26-INA-)") (class "Default")
      (node (ref "R18") (pin "1") (pinfunction "1_1") (pintype "input"))
      (node (ref "U26") (pin "1") (pinfunction "OUTA_1") (pintype "unspecified"))
      (node (ref "U26") (pin "2") (pinfunction "INA-_2") (pintype "unspecified"))
    )
    (net (code "57") (name "Net-(U26-INB-)") (class "Default")
      (node (ref "R18") (pin "2") (pinfunction "2_2") (pintype "input"))
      (node (ref "R19") (pin "1") (pinfunction "1_1") (pintype "input"))
      (node (ref "U26") (pin "6") (pinfunction "INB-_6") (pintype "unspecified"))
    )
    (net (code "58") (name "Net-(U26-OUTB)") (class "Default")
      (node (ref "R15") (pin "2") (pinfunction "2_2") (pintype "input"))
      (node (ref "R19") (pin "2") (pinfunction "2_2") (pintype "input"))
      (node (ref "U26") (pin "7") (pinfunction "OUTB_7") (pintype "unspecified"))
    )
    (net (code "59") (name "Net-(U27-INA+)") (class "Default")
      (node (ref "C24") (pin "1") (pinfunction "1_1") (pintype "input"))
      (node (ref "C26") (pin "1") (pinfunction "1_1") (pintype "input"))
      (node (ref "U27") (pin "3") (pinfunction "INA+_3") (pintype "unspecified"))
      (node (ref "U6") (pin "21") (pinfunction "REFTS_21") (pintype "unspecified"))
      (node (ref "U6") (pin "26") (pinfunction "VREF_26") (pintype "unspecified"))
    )
    (net (code "60") (name "Net-(U27-INA-)") (class "Default")
      (node (ref "R9") (pin "1") (pinfunction "1_1") (pintype "input"))
      (node (ref "U27") (pin "1") (pinfunction "OUTA_1") (pintype "unspecified"))
      (node (ref "U27") (pin "2") (pinfunction "INA-_2") (pintype "unspecified"))
    )
    (net (code "61") (name "Net-(U27-INB-)") (class "Default")
      (node (ref "R10") (pin "1") (pinfunction "1_1") (pintype "input"))
      (node (ref "R9") (pin "2") (pinfunction "2_2") (pintype "input"))
      (node (ref "U27") (pin "6") (pinfunction "INB-_6") (pintype "unspecified"))
    )
    (net (code "62") (name "Net-(U27-OUTB)") (class "Default")
      (node (ref "R10") (pin "2") (pinfunction "2_2") (pintype "input"))
      (node (ref "R8") (pin "2") (pinfunction "2_2") (pintype "input"))
      (node (ref "U27") (pin "7") (pinfunction "OUTB_7") (pintype "unspecified"))
    )
    (net (code "63") (name "Net-(power1-A)") (class "Default")
      (node (ref "R1") (pin "1") (pinfunction "1_1") (pintype "input"))
      (node (ref "power1") (pin "2") (pinfunction "A_2") (pintype "input"))
    )
    (net (code "64") (name "VCC") (class "Default")
      (node (ref "C16") (pin "2") (pinfunction "2_2") (pintype "input"))
      (node (ref "C17") (pin "2") (pinfunction "2_2") (pintype "input"))
      (node (ref "C18") (pin "2") (pinfunction "2_2") (pintype "input"))
      (node (ref "C21") (pin "1") (pinfunction "1_1") (pintype "input"))
      (node (ref "C23") (pin "1") (pinfunction "1_1") (pintype "input"))
      (node (ref "C36") (pin "1") (pinfunction "1_1") (pintype "input"))
      (node (ref "C38") (pin "1") (pinfunction "1_1") (pintype "input"))
      (node (ref "L3") (pin "2") (pinfunction "2_2") (pintype "unspecified"))
      (node (ref "L4") (pin "2") (pinfunction "2_2") (pintype "unspecified"))
      (node (ref "TP3") (pin "1") (pinfunction "1_1") (pintype "input"))
      (node (ref "U4") (pin "5") (pinfunction "VOUT_5") (pintype "unspecified"))
      (node (ref "U6") (pin "2") (pinfunction "DVDD_2") (pintype "unspecified"))
      (node (ref "U9") (pin "2") (pinfunction "DVDD_2") (pintype "unspecified"))
    )
    (net (code "65") (name "VCC+") (class "Default")
      (node (ref "C28") (pin "2") (pinfunction "2_2") (pintype "input"))
      (node (ref "C32") (pin "1") (pinfunction "1_1") (pintype "input"))
      (node (ref "C4") (pin "2") (pinfunction "2_2") (pintype "input"))
      (node (ref "C43") (pin "2") (pinfunction "2_2") (pintype "input"))
      (node (ref "C47") (pin "1") (pinfunction "1_1") (pintype "input"))
      (node (ref "C5") (pin "2") (pinfunction "2_2") (pintype "input"))
      (node (ref "C7") (pin "2") (pinfunction "2_2") (pintype "input"))
      (node (ref "C8") (pin "2") (pinfunction "2_2") (pintype "input"))
      (node (ref "TP1") (pin "1") (pinfunction "1_1") (pintype "input"))
      (node (ref "U1") (pin "5") (pinfunction "VOUT_5") (pintype "unspecified"))
      (node (ref "U20") (pin "5") (pinfunction "VS+_5") (pintype "unspecified"))
      (node (ref "U21") (pin "5") (pinfunction "VS+_5") (pintype "unspecified"))
      (node (ref "U26") (pin "8") (pinfunction "+VS_8") (pintype "unspecified"))
      (node (ref "U27") (pin "8") (pinfunction "+VS_8") (pintype "unspecified"))
      (node (ref "U3") (pin "2") (pinfunction "IN_2") (pintype "unspecified"))
      (node (ref "U3") (pin "5") (pinfunction "EN_5") (pintype "unspecified"))
    )
    (net (code "66") (name "VCC-") (class "Default")
      (node (ref "C11") (pin "2") (pinfunction "2_2") (pintype "input"))
      (node (ref "C12") (pin "2") (pinfunction "2_2") (pintype "input"))
      (node (ref "C19") (pin "2") (pinfunction "2_2") (pintype "input"))
      (node (ref "C33") (pin "1") (pinfunction "1_1") (pintype "input"))
      (node (ref "C34") (pin "2") (pinfunction "2_2") (pintype "input"))
      (node (ref "C50") (pin "1") (pinfunction "1_1") (pintype "input"))
      (node (ref "L2") (pin "2") (pinfunction "2_2") (pintype "unspecified"))
      (node (ref "TP2") (pin "1") (pinfunction "1_1") (pintype "input"))
      (node (ref "U20") (pin "2") (pinfunction "VS-_2") (pintype "unspecified"))
      (node (ref "U21") (pin "2") (pinfunction "VS-_2") (pintype "unspecified"))
      (node (ref "U26") (pin "4") (pinfunction "-VS_4") (pintype "unspecified"))
      (node (ref "U27") (pin "4") (pinfunction "-VS_4") (pintype "unspecified"))
    )
    (net (code "67") (name "VCC_5V") (class "Default")
      (node (ref "C13") (pin "2") (pinfunction "2_2") (pintype "input"))
      (node (ref "C14") (pin "2") (pinfunction "2_2") (pintype "input"))
      (node (ref "C15") (pin "2") (pinfunction "2_2") (pintype "input"))
      (node (ref "C2") (pin "2") (pinfunction "2_2") (pintype "input"))
      (node (ref "C3") (pin "2") (pinfunction "2_2") (pintype "input"))
      (node (ref "C6") (pin "2") (pinfunction "2_2") (pintype "input"))
      (node (ref "L1") (pin "2") (pinfunction "2_2") (pintype "unspecified"))
      (node (ref "R1") (pin "2") (pinfunction "2_2") (pintype "input"))
      (node (ref "U1") (pin "1") (pinfunction "VIN_1") (pintype "unspecified"))
      (node (ref "U1") (pin "3") (pinfunction "CE_3") (pintype "unspecified"))
      (node (ref "U4") (pin "1") (pinfunction "VIN_1") (pintype "unspecified"))
      (node (ref "U4") (pin "3") (pinfunction "CE_3") (pintype "unspecified"))
    )
    (net (code "68") (name "VCC_IN") (class "Default")
      (node (ref "CN1") (pin "2") (pinfunction "2_2") (pintype "unspecified"))
      (node (ref "L1") (pin "1") (pinfunction "1_1") (pintype "unspecified"))
    )
    (net (code "69") (name "unconnected-(C52-Pad1)") (class "Default")
      (node (ref "C52") (pin "1") (pinfunction "1_1") (pintype "input"))
    )
    (net (code "70") (name "unconnected-(C52-Pad2)") (class "Default")
      (node (ref "C52") (pin "2") (pinfunction "2_2") (pintype "input"))
    )
    (net (code "71") (name "unconnected-(C53-Pad1)") (class "Default")
      (node (ref "C53") (pin "1") (pinfunction "1_1") (pintype "input"))
    )
    (net (code "72") (name "unconnected-(C53-Pad2)") (class "Default")
      (node (ref "C53") (pin "2") (pinfunction "2_2") (pintype "input"))
    )
    (net (code "73") (name "unconnected-(C54-Pad1)") (class "Default")
      (node (ref "C54") (pin "1") (pinfunction "1_1") (pintype "input"))
    )
    (net (code "74") (name "unconnected-(C54-Pad2)") (class "Default")
      (node (ref "C54") (pin "2") (pinfunction "2_2") (pintype "input"))
    )
    (net (code "75") (name "unconnected-(CN1-Pad15)") (class "Default")
      (node (ref "CN1") (pin "15") (pinfunction "15_15") (pintype "unspecified+no_connect"))
    )
    (net (code "76") (name "unconnected-(CN1-Pad21)") (class "Default")
      (node (ref "CN1") (pin "21") (pinfunction "21_21") (pintype "unspecified+no_connect"))
    )
    (net (code "77") (name "unconnected-(CN1-Pad22)") (class "Default")
      (node (ref "CN1") (pin "22") (pinfunction "22_22") (pintype "unspecified+no_connect"))
    )
    (net (code "78") (name "unconnected-(CN1-Pad23)") (class "Default")
      (node (ref "CN1") (pin "23") (pinfunction "23_23") (pintype "unspecified+no_connect"))
    )
    (net (code "79") (name "unconnected-(U1-NC-Pad4)") (class "Default")
      (node (ref "U1") (pin "4") (pinfunction "NC_4") (pintype "unspecified+no_connect"))
    )
    (net (code "80") (name "unconnected-(U4-NC-Pad4)") (class "Default")
      (node (ref "U4") (pin "4") (pinfunction "NC_4") (pintype "unspecified+no_connect"))
    )
  )
)
